# Motorsteuerung_v3.net
KiCad netlist of a schematic drawn in EAGLE
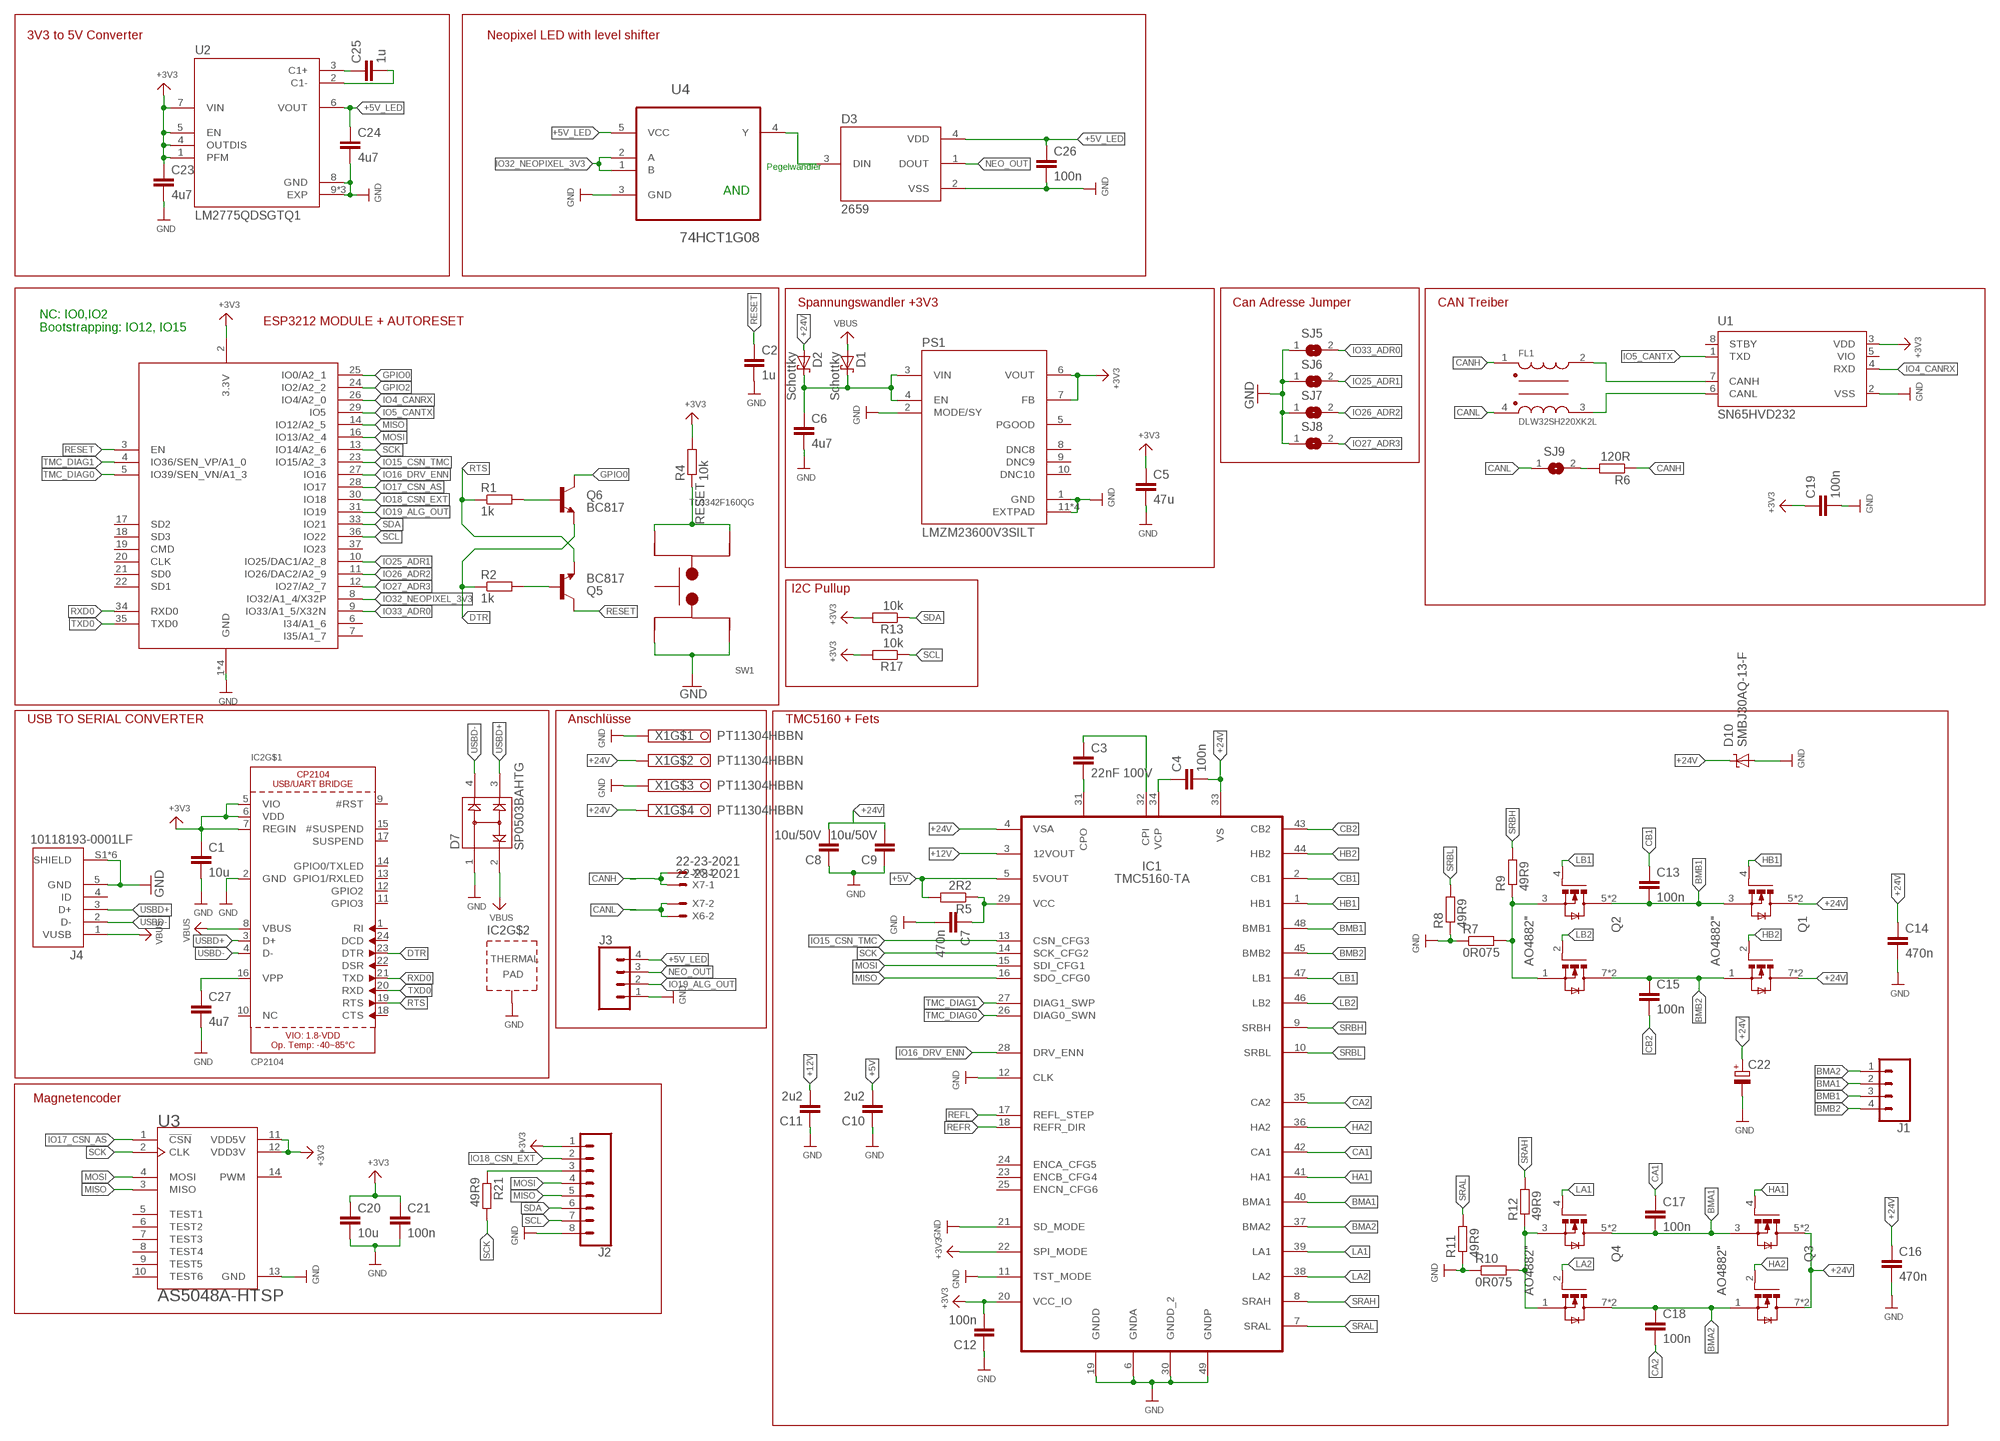
[diagram p0: schematic, sheet 1]

(export (version "E")
  (design (tool "Eeschema 10.0.6"))
  (components
    (comp (ref "C1")
      (value "10u")
      (footprint "eagle-import:C0805")
      (libsource (lib "eagle-import") (part "C-EUC0805"))
    )
    (comp (ref "C2")
      (value "1u")
      (footprint "eagle-import:C0805")
      (libsource (lib "eagle-import") (part "C-EUC0805"))
    )
    (comp (ref "C3")
      (value "22nF 100V")
      (footprint "eagle-import:C0805")
      (libsource (lib "eagle-import") (part "C-EUC0805"))
    )
    (comp (ref "C4")
      (value "100n")
      (footprint "eagle-import:C0805")
      (libsource (lib "eagle-import") (part "C-EUC0805"))
    )
    (comp (ref "C5")
      (value "47u")
      (footprint "eagle-import:C0805")
      (libsource (lib "eagle-import") (part "C-EUC0805"))
    )
    (comp (ref "C6")
      (value "4u7")
      (footprint "eagle-import:C0805")
      (libsource (lib "eagle-import") (part "C-EUC0805"))
    )
    (comp (ref "C7")
      (value "470n")
      (footprint "eagle-import:C0805")
      (libsource (lib "eagle-import") (part "C-EUC0805"))
    )
    (comp (ref "C8")
      (value "10u/50V")
      (footprint "eagle-import:C0805")
      (libsource (lib "eagle-import") (part "C-EUC0805"))
    )
    (comp (ref "C9")
      (value "10u/50V")
      (footprint "eagle-import:C0805")
      (libsource (lib "eagle-import") (part "C-EUC0805"))
    )
    (comp (ref "C10")
      (value "2u2")
      (footprint "eagle-import:C0805")
      (libsource (lib "eagle-import") (part "C-EUC0805"))
    )
    (comp (ref "C11")
      (value "2u2")
      (footprint "eagle-import:C0805")
      (libsource (lib "eagle-import") (part "C-EUC0805"))
    )
    (comp (ref "C12")
      (value "100n")
      (footprint "eagle-import:C0805")
      (libsource (lib "eagle-import") (part "C-EUC0805"))
    )
    (comp (ref "C13")
      (value "100n")
      (footprint "eagle-import:C0805")
      (libsource (lib "eagle-import") (part "C-EUC0805"))
    )
    (comp (ref "C14")
      (value "470n")
      (footprint "eagle-import:C0805")
      (libsource (lib "eagle-import") (part "C-EUC0805"))
    )
    (comp (ref "C15")
      (value "100n")
      (footprint "eagle-import:C0805")
      (libsource (lib "eagle-import") (part "C-EUC0805"))
    )
    (comp (ref "C16")
      (value "470n")
      (footprint "eagle-import:C0805")
      (libsource (lib "eagle-import") (part "C-EUC0805"))
    )
    (comp (ref "C17")
      (value "100n")
      (footprint "eagle-import:C0805")
      (libsource (lib "eagle-import") (part "C-EUC0805"))
    )
    (comp (ref "C18")
      (value "100n")
      (footprint "eagle-import:C0805")
      (libsource (lib "eagle-import") (part "C-EUC0805"))
    )
    (comp (ref "C19")
      (value "100n")
      (footprint "eagle-import:C0805")
      (libsource (lib "eagle-import") (part "C-EUC0805"))
    )
    (comp (ref "C20")
      (value "10u")
      (footprint "eagle-import:C0805")
      (libsource (lib "eagle-import") (part "C-EUC0805"))
    )
    (comp (ref "C21")
      (value "100n")
      (footprint "eagle-import:C0805")
      (libsource (lib "eagle-import") (part "C-EUC0805"))
    )
    (comp (ref "C22")
      (value "CPOL-EUE5-10.5")
      (footprint "eagle-import:E5-10,5")
      (libsource (lib "eagle-import") (part "CPOL-EUE5-10.5"))
    )
    (comp (ref "C23")
      (value "4u7")
      (footprint "eagle-import:C0805")
      (libsource (lib "eagle-import") (part "C-EUC0805"))
    )
    (comp (ref "C24")
      (value "4u7")
      (footprint "eagle-import:C0805")
      (libsource (lib "eagle-import") (part "C-EUC0805"))
    )
    (comp (ref "C25")
      (value "1u")
      (footprint "eagle-import:C0805")
      (libsource (lib "eagle-import") (part "C-EUC0805"))
    )
    (comp (ref "C26")
      (value "100n")
      (footprint "eagle-import:C0805")
      (libsource (lib "eagle-import") (part "C-EUC0805"))
    )
    (comp (ref "C27")
      (value "4u7")
      (footprint "eagle-import:C0805")
      (libsource (lib "eagle-import") (part "C-EUC0805"))
    )
    (comp (ref "D1")
      (value "Schottky")
      (footprint "eagle-import:SMB")
      (libsource (lib "eagle-import") (part "SCHOTTKY-DIODESMD"))
    )
    (comp (ref "D2")
      (value "Schottky")
      (footprint "eagle-import:SMB")
      (libsource (lib "eagle-import") (part "SCHOTTKY-DIODESMD"))
    )
    (comp (ref "D3")
      (value "2659")
      (footprint "eagle-import:2659")
      (fields (field (name "MF") "Adafruit Industries"))
      (libsource (lib "eagle-import") (part "2659"))
    )
    (comp (ref "D7")
      (value "SP0503BAHTG")
      (footprint "eagle-import:SOT143")
      (fields (field (name "MF") "Littelfuse Inc."))
      (libsource (lib "eagle-import") (part "SP0503BAHTG"))
    )
    (comp (ref "D10")
      (value "SMBJ30AQ-13-F")
      (footprint "eagle-import:SMBJ")
      (libsource (lib "eagle-import") (part "SUPPRESSOR-SMBJ"))
    )
    (comp (ref "FL1")
      (value "DLW32SH220XK2L")
      (footprint "eagle-import:FIL_DLW32SH110XK2L")
      (fields (field (name "MF") "Murata") (field (name "MP") "DLW32SH110XK2L"))
      (libsource (lib "eagle-import") (part "DLW32SH110XK2L"))
    )
    (comp (ref "IC1")
      (value "TMC5160-TA")
      (footprint "eagle-import:TQFP48-EP")
      (fields (field (name "MF") "Trinamic Motion"))
      (libsource (lib "eagle-import") (part "TMC5160-TA"))
    )
    (comp (ref "IC2")
      (value "CP2104")
      (footprint "eagle-import:QFN24_4MM_SMSC")
      (libsource (lib "eagle-import") (part "CP2104"))
    )
    (comp (ref "J1")
      (value "CONN_04")
      (footprint "eagle-import:1X04")
      (libsource (lib "eagle-import") (part "CONN_04"))
    )
    (comp (ref "J2")
      (value "CONN_08BM08B-SRSS-TB")
      (footprint "eagle-import:BM08B-SRSS-TB")
      (libsource (lib "eagle-import") (part "CONN_08BM08B-SRSS-TB"))
    )
    (comp (ref "J3")
      (value "CONN_041.27MM")
      (footprint "eagle-import:1X04_1.27MM")
      (libsource (lib "eagle-import") (part "CONN_041.27MM"))
    )
    (comp (ref "J4")
      (value "10118193-0001LF")
      (footprint "eagle-import:FCI_10118193-0001LF")
      (fields (field (name "MF") "Amphenol ICC (FCI)"))
      (libsource (lib "eagle-import") (part "10118193-0001LF"))
    )
    (comp (ref "PS1")
      (value "LMZM23600V3SILT")
      (footprint "eagle-import:CONV_LMZM23600V3SILT")
      (fields (field (name "MF") "Texas Instruments"))
      (libsource (lib "eagle-import") (part "LMZM23600V3SILT"))
    )
    (comp (ref "Q1")
      (value "AO4882\"")
      (footprint "eagle-import:SOIC8")
      (libsource (lib "eagle-import") (part "AO4882{dblquote}"))
    )
    (comp (ref "Q2")
      (value "AO4882\"")
      (footprint "eagle-import:SOIC8")
      (libsource (lib "eagle-import") (part "AO4882{dblquote}"))
    )
    (comp (ref "Q3")
      (value "AO4882\"")
      (footprint "eagle-import:SOIC8")
      (libsource (lib "eagle-import") (part "AO4882{dblquote}"))
    )
    (comp (ref "Q4")
      (value "AO4882\"")
      (footprint "eagle-import:SOIC8")
      (libsource (lib "eagle-import") (part "AO4882{dblquote}"))
    )
    (comp (ref "Q5")
      (value "BC817")
      (footprint "eagle-import:SOT23-3")
      (libsource (lib "eagle-import") (part "TRANSISTOR_NPNSOT23-3"))
    )
    (comp (ref "Q6")
      (value "BC817")
      (footprint "eagle-import:SOT23-3")
      (libsource (lib "eagle-import") (part "TRANSISTOR_NPNSOT23-3"))
    )
    (comp (ref "R1")
      (value "1k")
      (footprint "eagle-import:R0805")
      (libsource (lib "eagle-import") (part "R-EU_R0805"))
    )
    (comp (ref "R2")
      (value "1k")
      (footprint "eagle-import:R0805")
      (libsource (lib "eagle-import") (part "R-EU_R0805"))
    )
    (comp (ref "R4")
      (value "10k")
      (footprint "eagle-import:R0805")
      (libsource (lib "eagle-import") (part "R-EU_R0805"))
    )
    (comp (ref "R5")
      (value "2R2")
      (footprint "eagle-import:R0805")
      (libsource (lib "eagle-import") (part "R-EU_R0805"))
    )
    (comp (ref "R6")
      (value "120R")
      (footprint "eagle-import:R0805")
      (libsource (lib "eagle-import") (part "R-EU_R0805"))
    )
    (comp (ref "R7")
      (value "0R075")
      (footprint "eagle-import:R1206")
      (libsource (lib "eagle-import") (part "R-EU_R1206"))
    )
    (comp (ref "R8")
      (value "49R9")
      (footprint "eagle-import:R0805")
      (libsource (lib "eagle-import") (part "R-EU_R0805"))
    )
    (comp (ref "R9")
      (value "49R9")
      (footprint "eagle-import:R0805")
      (libsource (lib "eagle-import") (part "R-EU_R0805"))
    )
    (comp (ref "R10")
      (value "0R075")
      (footprint "eagle-import:R1206")
      (libsource (lib "eagle-import") (part "R-EU_R1206"))
    )
    (comp (ref "R11")
      (value "49R9")
      (footprint "eagle-import:R0805")
      (libsource (lib "eagle-import") (part "R-EU_R0805"))
    )
    (comp (ref "R12")
      (value "49R9")
      (footprint "eagle-import:R0805")
      (libsource (lib "eagle-import") (part "R-EU_R0805"))
    )
    (comp (ref "R13")
      (value "10k")
      (footprint "eagle-import:R0805")
      (libsource (lib "eagle-import") (part "R-EU_R0805"))
    )
    (comp (ref "R17")
      (value "10k")
      (footprint "eagle-import:R0805")
      (libsource (lib "eagle-import") (part "R-EU_R0805"))
    )
    (comp (ref "R21")
      (value "49R9")
      (footprint "eagle-import:R0805")
      (libsource (lib "eagle-import") (part "R-EU_R0805"))
    )
    (comp (ref "SJ5") (value "SJ") (footprint "eagle-import:SJ") (libsource (lib "eagle-import") (part "SJ")))
    (comp (ref "SJ6") (value "SJ") (footprint "eagle-import:SJ") (libsource (lib "eagle-import") (part "SJ")))
    (comp (ref "SJ7") (value "SJ") (footprint "eagle-import:SJ") (libsource (lib "eagle-import") (part "SJ")))
    (comp (ref "SJ8") (value "SJ") (footprint "eagle-import:SJ") (libsource (lib "eagle-import") (part "SJ")))
    (comp (ref "SJ9") (value "SJ") (footprint "eagle-import:SJ") (libsource (lib "eagle-import") (part "SJ")))
    (comp (ref "SW1")
      (value "TL3342F160QG")
      (footprint "eagle-import:SW_TL3342F160QG")
      (fields (field (name "MF") "E-Switch"))
      (libsource (lib "eagle-import") (part "TL3342F160QG"))
    )
    (comp (ref "U1")
      (value "SN65HVD232")
      (footprint "eagle-import:SOIC127P600X175-8N")
      (fields (field (name "MF") "Microchip") (field (name "MP") "MCP2562-E/SN"))
      (libsource (lib "eagle-import") (part "MCP2562-E/SN"))
    )
    (comp (ref "U2")
      (value "LM2775QDSGTQ1")
      (footprint "eagle-import:SON50P200X200X80-9N")
      (fields (field (name "MF") "Texas Instruments"))
      (libsource (lib "eagle-import") (part "LM2775QDSGTQ1"))
    )
    (comp (ref "U3")
      (value "AS5048A-HTSP")
      (footprint "eagle-import:SOP65P640X120-14N")
      (fields (field (name "MF") "ams"))
      (libsource (lib "eagle-import") (part "AS5048A-HTSP"))
    )
    (comp (ref "U4")
      (value "74HCT1G08")
      (footprint "eagle-import:SOT65P210X110-5N")
      (fields (field (name "MF") "Nexperia") (field (name "MP") "74LVC1G00GW"))
      (libsource (lib "eagle-import") (part "74LVC1G00GW"))
    )
    (comp (ref "X1")
      (value "PT11304HBBN")
      (footprint "eagle-import:TYP184_FT")
      (libsource (lib "eagle-import") (part "TYP184"))
    )
    (comp (ref "X2")
      (value "ESP32_WROOM32_SKINNY")
      (footprint "eagle-import:WROOM32_SKINNY")
      (libsource (lib "eagle-import") (part "ESP32_WROOM32_SKINNY"))
    )
    (comp (ref "X6")
      (value "22-23-2021")
      (footprint "eagle-import:22-23-2021")
      (fields (field (name "MF") "MOLEX"))
      (libsource (lib "eagle-import") (part "22-23-2021"))
    )
    (comp (ref "X7")
      (value "22-23-2021")
      (footprint "eagle-import:22-23-2021")
      (fields (field (name "MF") "MOLEX"))
      (libsource (lib "eagle-import") (part "22-23-2021"))
    )
  )
  (nets
    (net (code "1") (name "+3V3") (class "Default")
      (node (ref "C1") (pin "1") (pinfunction "1_1") (pintype "passive"))
      (node (ref "C12") (pin "2") (pinfunction "2_2") (pintype "passive"))
      (node (ref "C19") (pin "1") (pinfunction "1_1") (pintype "passive"))
      (node (ref "C20") (pin "1") (pinfunction "1_1") (pintype "passive"))
      (node (ref "C21") (pin "1") (pinfunction "1_1") (pintype "passive"))
      (node (ref "C23") (pin "1") (pinfunction "1_1") (pintype "passive"))
      (node (ref "C5") (pin "1") (pinfunction "1_1") (pintype "passive"))
      (node (ref "IC1") (pin "20") (pinfunction "VCC_IO_20") (pintype "power_in"))
      (node (ref "IC1") (pin "22") (pinfunction "SPI_MODE_22") (pintype "input"))
      (node (ref "IC2") (pin "5") (pinfunction "VIO_5") (pintype "power_in"))
      (node (ref "IC2") (pin "6") (pinfunction "VDD_6") (pintype "power_in"))
      (node (ref "IC2") (pin "7") (pinfunction "REGIN_7") (pintype "power_in"))
      (node (ref "J2") (pin "1") (pinfunction "1_1") (pintype "passive"))
      (node (ref "PS1") (pin "6") (pinfunction "VOUT_6") (pintype "output"))
      (node (ref "PS1") (pin "7") (pinfunction "FB_7") (pintype "input"))
      (node (ref "R13") (pin "2") (pinfunction "2_2") (pintype "passive"))
      (node (ref "R17") (pin "2") (pinfunction "2_2") (pintype "passive"))
      (node (ref "R4") (pin "2") (pinfunction "2_2") (pintype "passive"))
      (node (ref "U1") (pin "3") (pinfunction "VDD_3") (pintype "power_in"))
      (node (ref "U2") (pin "1") (pinfunction "PFM_1") (pintype "input"))
      (node (ref "U2") (pin "4") (pinfunction "OUTDIS_4") (pintype "input"))
      (node (ref "U2") (pin "5") (pinfunction "EN_5") (pintype "input"))
      (node (ref "U2") (pin "7") (pinfunction "VIN_7") (pintype "input"))
      (node (ref "U3") (pin "11") (pinfunction "VDD5V_11") (pintype "power_in"))
      (node (ref "U3") (pin "12") (pinfunction "VDD3V_12") (pintype "power_in"))
      (node (ref "X2") (pin "2") (pinfunction "3.3V_2") (pintype "passive"))
    )
    (net (code "2") (name "+5V") (class "Default")
      (node (ref "C10") (pin "2") (pinfunction "2_2") (pintype "passive"))
      (node (ref "IC1") (pin "5") (pinfunction "5VOUT_5") (pintype "bidirectional"))
      (node (ref "R5") (pin "2") (pinfunction "2_2") (pintype "passive"))
    )
    (net (code "3") (name "+5V_LED") (class "Default")
      (node (ref "C24") (pin "1") (pinfunction "1_1") (pintype "passive"))
      (node (ref "C26") (pin "1") (pinfunction "1_1") (pintype "passive"))
      (node (ref "D3") (pin "4") (pinfunction "VDD_4") (pintype "power_in"))
      (node (ref "J3") (pin "4") (pinfunction "4_4") (pintype "passive"))
      (node (ref "U2") (pin "6") (pinfunction "VOUT_6") (pintype "output"))
      (node (ref "U4") (pin "5") (pinfunction "VCC_5") (pintype "power_in"))
    )
    (net (code "4") (name "+12V") (class "Default")
      (node (ref "C11") (pin "2") (pinfunction "2_2") (pintype "passive"))
      (node (ref "IC1") (pin "3") (pinfunction "12VOUT_3") (pintype "bidirectional"))
    )
    (net (code "5") (name "+24V") (class "Default")
      (node (ref "C14") (pin "1") (pinfunction "1_1") (pintype "passive"))
      (node (ref "C16") (pin "1") (pinfunction "1_1") (pintype "passive"))
      (node (ref "C22") (pin "+") (pinfunction "+_+") (pintype "passive"))
      (node (ref "C4") (pin "2") (pinfunction "2_2") (pintype "passive"))
      (node (ref "C8") (pin "2") (pinfunction "2_2") (pintype "passive"))
      (node (ref "C9") (pin "2") (pinfunction "2_2") (pintype "passive"))
      (node (ref "D10") (pin "C") (pinfunction "C_C") (pintype "passive"))
      (node (ref "D2") (pin "A") (pinfunction "A_A") (pintype "passive"))
      (node (ref "IC1") (pin "33") (pinfunction "VS_33") (pintype "power_in"))
      (node (ref "IC1") (pin "4") (pinfunction "VSA_4") (pintype "power_in"))
      (node (ref "Q1") (pin "5") (pinfunction "D1_5") (pintype "passive"))
      (node (ref "Q1") (pin "6") (pinfunction "D1_6") (pintype "passive"))
      (node (ref "Q1") (pin "7") (pinfunction "D2_7") (pintype "passive"))
      (node (ref "Q1") (pin "8") (pinfunction "D2_8") (pintype "passive"))
      (node (ref "Q3") (pin "5") (pinfunction "D1_5") (pintype "passive"))
      (node (ref "Q3") (pin "6") (pinfunction "D1_6") (pintype "passive"))
      (node (ref "Q3") (pin "7") (pinfunction "D2_7") (pintype "passive"))
      (node (ref "Q3") (pin "8") (pinfunction "D2_8") (pintype "passive"))
      (node (ref "X1") (pin "2") (pinfunction "K_2") (pintype "passive"))
      (node (ref "X1") (pin "4") (pinfunction "K_4") (pintype "passive"))
    )
    (net (code "6") (name "/VIO") (class "Default")
      (node (ref "U1") (pin "5") (pinfunction "VIO_5") (pintype "power_in"))
    )
    (net (code "7") (name "BMA1") (class "Default")
      (node (ref "C17") (pin "2") (pinfunction "2_2") (pintype "passive"))
      (node (ref "IC1") (pin "40") (pinfunction "BMA1_40") (pintype "input"))
      (node (ref "J1") (pin "2") (pinfunction "2_2") (pintype "passive"))
      (node (ref "Q3") (pin "3") (pinfunction "S1_3") (pintype "passive"))
      (node (ref "Q4") (pin "5") (pinfunction "D1_5") (pintype "passive"))
      (node (ref "Q4") (pin "6") (pinfunction "D1_6") (pintype "passive"))
    )
    (net (code "8") (name "BMA2") (class "Default")
      (node (ref "C18") (pin "1") (pinfunction "1_1") (pintype "passive"))
      (node (ref "IC1") (pin "37") (pinfunction "BMA2_37") (pintype "input"))
      (node (ref "J1") (pin "1") (pinfunction "1_1") (pintype "passive"))
      (node (ref "Q3") (pin "1") (pinfunction "S2_1") (pintype "passive"))
      (node (ref "Q4") (pin "7") (pinfunction "D2_7") (pintype "passive"))
      (node (ref "Q4") (pin "8") (pinfunction "D2_8") (pintype "passive"))
    )
    (net (code "9") (name "BMB1") (class "Default")
      (node (ref "C13") (pin "2") (pinfunction "2_2") (pintype "passive"))
      (node (ref "IC1") (pin "48") (pinfunction "BMB1_48") (pintype "input"))
      (node (ref "J1") (pin "3") (pinfunction "3_3") (pintype "passive"))
      (node (ref "Q1") (pin "3") (pinfunction "S1_3") (pintype "passive"))
      (node (ref "Q2") (pin "5") (pinfunction "D1_5") (pintype "passive"))
      (node (ref "Q2") (pin "6") (pinfunction "D1_6") (pintype "passive"))
    )
    (net (code "10") (name "BMB2") (class "Default")
      (node (ref "C15") (pin "1") (pinfunction "1_1") (pintype "passive"))
      (node (ref "IC1") (pin "45") (pinfunction "BMB2_45") (pintype "input"))
      (node (ref "J1") (pin "4") (pinfunction "4_4") (pintype "passive"))
      (node (ref "Q1") (pin "1") (pinfunction "S2_1") (pintype "passive"))
      (node (ref "Q2") (pin "7") (pinfunction "D2_7") (pintype "passive"))
      (node (ref "Q2") (pin "8") (pinfunction "D2_8") (pintype "passive"))
    )
    (net (code "11") (name "CA1") (class "Default")
      (node (ref "C17") (pin "1") (pinfunction "1_1") (pintype "passive"))
      (node (ref "IC1") (pin "42") (pinfunction "CA1_42") (pintype "input"))
    )
    (net (code "12") (name "CA2") (class "Default")
      (node (ref "C18") (pin "2") (pinfunction "2_2") (pintype "passive"))
      (node (ref "IC1") (pin "35") (pinfunction "CA2_35") (pintype "input"))
    )
    (net (code "13") (name "CANH") (class "Default")
      (node (ref "FL1") (pin "1") (pinfunction "1_1") (pintype "passive"))
      (node (ref "R6") (pin "1") (pinfunction "1_1") (pintype "passive"))
      (node (ref "X6") (pin "1") (pinfunction "S_1") (pintype "passive"))
      (node (ref "X7") (pin "1") (pinfunction "S_1") (pintype "passive"))
    )
    (net (code "14") (name "CANL") (class "Default")
      (node (ref "FL1") (pin "4") (pinfunction "4_4") (pintype "passive"))
      (node (ref "SJ9") (pin "1") (pinfunction "1_1") (pintype "passive"))
      (node (ref "X6") (pin "2") (pinfunction "S_2") (pintype "passive"))
      (node (ref "X7") (pin "2") (pinfunction "S_2") (pintype "passive"))
    )
    (net (code "15") (name "CB1") (class "Default")
      (node (ref "C13") (pin "1") (pinfunction "1_1") (pintype "passive"))
      (node (ref "IC1") (pin "2") (pinfunction "CB1_2") (pintype "input"))
    )
    (net (code "16") (name "CB2") (class "Default")
      (node (ref "C15") (pin "2") (pinfunction "2_2") (pintype "passive"))
      (node (ref "IC1") (pin "43") (pinfunction "CB2_43") (pintype "input"))
    )
    (net (code "17") (name "DTR") (class "Default")
      (node (ref "IC2") (pin "23") (pinfunction "DTR_23") (pintype "output"))
      (node (ref "Q6") (pin "2") (pinfunction "E_2") (pintype "passive"))
      (node (ref "R2") (pin "1") (pinfunction "1_1") (pintype "passive"))
    )
    (net (code "18") (name "GND") (class "Default")
      (node (ref "C1") (pin "2") (pinfunction "2_2") (pintype "passive"))
      (node (ref "C10") (pin "1") (pinfunction "1_1") (pintype "passive"))
      (node (ref "C11") (pin "1") (pinfunction "1_1") (pintype "passive"))
      (node (ref "C12") (pin "1") (pinfunction "1_1") (pintype "passive"))
      (node (ref "C14") (pin "2") (pinfunction "2_2") (pintype "passive"))
      (node (ref "C16") (pin "2") (pinfunction "2_2") (pintype "passive"))
      (node (ref "C19") (pin "2") (pinfunction "2_2") (pintype "passive"))
      (node (ref "C2") (pin "2") (pinfunction "2_2") (pintype "passive"))
      (node (ref "C20") (pin "2") (pinfunction "2_2") (pintype "passive"))
      (node (ref "C21") (pin "2") (pinfunction "2_2") (pintype "passive"))
      (node (ref "C22") (pin "-") (pinfunction "-_-") (pintype "passive"))
      (node (ref "C23") (pin "2") (pinfunction "2_2") (pintype "passive"))
      (node (ref "C24") (pin "2") (pinfunction "2_2") (pintype "passive"))
      (node (ref "C26") (pin "2") (pinfunction "2_2") (pintype "passive"))
      (node (ref "C27") (pin "2") (pinfunction "2_2") (pintype "passive"))
      (node (ref "C5") (pin "2") (pinfunction "2_2") (pintype "passive"))
      (node (ref "C6") (pin "2") (pinfunction "2_2") (pintype "passive"))
      (node (ref "C7") (pin "2") (pinfunction "2_2") (pintype "passive"))
      (node (ref "C8") (pin "1") (pinfunction "1_1") (pintype "passive"))
      (node (ref "C9") (pin "1") (pinfunction "1_1") (pintype "passive"))
      (node (ref "D10") (pin "A") (pinfunction "A_A") (pintype "passive"))
      (node (ref "D3") (pin "2") (pinfunction "VSS_2") (pintype "power_in"))
      (node (ref "D7") (pin "1") (pinfunction "1_1") (pintype "passive"))
      (node (ref "IC1") (pin "11") (pinfunction "TST_MODE_11") (pintype "input"))
      (node (ref "IC1") (pin "12") (pinfunction "CLK_12") (pintype "input"))
      (node (ref "IC1") (pin "19") (pinfunction "GNDD_19") (pintype "power_in"))
      (node (ref "IC1") (pin "21") (pinfunction "SD_MODE_21") (pintype "input"))
      (node (ref "IC1") (pin "30") (pinfunction "GNDD_2_30") (pintype "power_in"))
      (node (ref "IC1") (pin "49") (pinfunction "GNDP_49") (pintype "power_in"))
      (node (ref "IC1") (pin "6") (pinfunction "GNDA_6") (pintype "power_in"))
      (node (ref "IC2") (pin "2") (pinfunction "GND_2") (pintype "power_in"))
      (node (ref "IC2") (pin "THERM") (pinfunction "TP_THERM") (pintype "power_in"))
      (node (ref "J2") (pin "8") (pinfunction "8_8") (pintype "passive"))
      (node (ref "J3") (pin "1") (pinfunction "1_1") (pintype "passive"))
      (node (ref "J4") (pin "5") (pinfunction "GND_5") (pintype "passive"))
      (node (ref "J4") (pin "S1") (pinfunction "SHIELD_S1") (pintype "passive"))
      (node (ref "J4") (pin "S2") (pinfunction "SHIELD_S2") (pintype "passive"))
      (node (ref "J4") (pin "S3") (pinfunction "SHIELD_S3") (pintype "passive"))
      (node (ref "J4") (pin "S4") (pinfunction "SHIELD_S4") (pintype "passive"))
      (node (ref "J4") (pin "S5") (pinfunction "SHIELD_S5") (pintype "passive"))
      (node (ref "J4") (pin "S6") (pinfunction "SHIELD_S6") (pintype "passive"))
      (node (ref "PS1") (pin "1") (pinfunction "GND_1") (pintype "power_in"))
      (node (ref "PS1") (pin "11") (pinfunction "EXTPAD_11") (pintype "power_in"))
      (node (ref "PS1") (pin "11_1") (pinfunction "EXTPAD_11_1") (pintype "power_in"))
      (node (ref "PS1") (pin "11_2") (pinfunction "EXTPAD_11_2") (pintype "power_in"))
      (node (ref "PS1") (pin "11_3") (pinfunction "EXTPAD_11_3") (pintype "power_in"))
      (node (ref "PS1") (pin "2") (pinfunction "MODE/SY_2") (pintype "input"))
      (node (ref "R10") (pin "1") (pinfunction "1_1") (pintype "passive"))
      (node (ref "R11") (pin "1") (pinfunction "1_1") (pintype "passive"))
      (node (ref "R7") (pin "1") (pinfunction "1_1") (pintype "passive"))
      (node (ref "R8") (pin "1") (pinfunction "1_1") (pintype "passive"))
      (node (ref "SJ5") (pin "1") (pinfunction "1_1") (pintype "passive"))
      (node (ref "SJ6") (pin "1") (pinfunction "1_1") (pintype "passive"))
      (node (ref "SJ7") (pin "1") (pinfunction "1_1") (pintype "passive"))
      (node (ref "SJ8") (pin "1") (pinfunction "1_1") (pintype "passive"))
      (node (ref "SW1") (pin "3") (pinfunction "3_3") (pintype "passive"))
      (node (ref "SW1") (pin "4") (pinfunction "4_4") (pintype "passive"))
      (node (ref "U1") (pin "2") (pinfunction "VSS_2") (pintype "power_in"))
      (node (ref "U2") (pin "8") (pinfunction "GND_8") (pintype "power_in"))
      (node (ref "U2") (pin "9") (pinfunction "EXP_9") (pintype "power_in"))
      (node (ref "U2") (pin "9_1") (pinfunction "EXP_9_1") (pintype "power_in"))
      (node (ref "U2") (pin "9_2") (pinfunction "EXP_9_2") (pintype "power_in"))
      (node (ref "U3") (pin "13") (pinfunction "GND_13") (pintype "passive"))
      (node (ref "U4") (pin "3") (pinfunction "GND_3") (pintype "passive"))
      (node (ref "X1") (pin "1") (pinfunction "K_1") (pintype "passive"))
      (node (ref "X1") (pin "3") (pinfunction "K_3") (pintype "passive"))
      (node (ref "X2") (pin "1") (pinfunction "GND_1") (pintype "passive"))
      (node (ref "X2") (pin "15") (pinfunction "GND_15") (pintype "passive"))
      (node (ref "X2") (pin "38") (pinfunction "GND_38") (pintype "passive"))
      (node (ref "X2") (pin "P$1") (pinfunction "GND_P$1") (pintype "passive"))
    )
    (net (code "19") (name "GPIO0") (class "Default")
      (node (ref "Q6") (pin "3") (pinfunction "C_3") (pintype "passive"))
      (node (ref "X2") (pin "25") (pinfunction "IO0/A2_1_25") (pintype "bidirectional"))
    )
    (net (code "20") (name "GPIO2") (class "Default")
      (node (ref "X2") (pin "24") (pinfunction "IO2/A2_2_24") (pintype "bidirectional"))
    )
    (net (code "21") (name "HA1") (class "Default")
      (node (ref "IC1") (pin "41") (pinfunction "HA1_41") (pintype "output"))
      (node (ref "Q3") (pin "4") (pinfunction "G1_4") (pintype "passive"))
    )
    (net (code "22") (name "HA2") (class "Default")
      (node (ref "IC1") (pin "36") (pinfunction "HA2_36") (pintype "output"))
      (node (ref "Q3") (pin "2") (pinfunction "G2_2") (pintype "passive"))
    )
    (net (code "23") (name "HB1") (class "Default")
      (node (ref "IC1") (pin "1") (pinfunction "HB1_1") (pintype "output"))
      (node (ref "Q1") (pin "4") (pinfunction "G1_4") (pintype "passive"))
    )
    (net (code "24") (name "HB2") (class "Default")
      (node (ref "IC1") (pin "44") (pinfunction "HB2_44") (pintype "output"))
      (node (ref "Q1") (pin "2") (pinfunction "G2_2") (pintype "passive"))
    )
    (net (code "25") (name "IO4_CANRX") (class "Default")
      (node (ref "U1") (pin "4") (pinfunction "RXD_4") (pintype "output"))
      (node (ref "X2") (pin "26") (pinfunction "IO4/A2_0_26") (pintype "bidirectional"))
    )
    (net (code "26") (name "IO5_CANTX") (class "Default")
      (node (ref "U1") (pin "1") (pinfunction "TXD_1") (pintype "input"))
      (node (ref "X2") (pin "29") (pinfunction "IO5_29") (pintype "bidirectional"))
    )
    (net (code "27") (name "IO15_CSN_TMC") (class "Default")
      (node (ref "IC1") (pin "13") (pinfunction "CSN_CFG3_13") (pintype "input"))
      (node (ref "X2") (pin "23") (pinfunction "IO15/A2_3_23") (pintype "bidirectional"))
    )
    (net (code "28") (name "IO16_DRV_ENN") (class "Default")
      (node (ref "IC1") (pin "28") (pinfunction "DRV_ENN_28") (pintype "input"))
      (node (ref "X2") (pin "27") (pinfunction "IO16_27") (pintype "bidirectional"))
    )
    (net (code "29") (name "IO17_CSN_AS") (class "Default")
      (node (ref "U3") (pin "1") (pinfunction "~{CSN}_1") (pintype "input"))
      (node (ref "X2") (pin "28") (pinfunction "IO17_28") (pintype "bidirectional"))
    )
    (net (code "30") (name "IO18_CSN_EXT") (class "Default")
      (node (ref "J2") (pin "2") (pinfunction "2_2") (pintype "passive"))
      (node (ref "X2") (pin "30") (pinfunction "IO18_30") (pintype "bidirectional"))
    )
    (net (code "31") (name "IO19_ALG_OUT") (class "Default")
      (node (ref "J3") (pin "2") (pinfunction "2_2") (pintype "passive"))
      (node (ref "X2") (pin "31") (pinfunction "IO19_31") (pintype "bidirectional"))
    )
    (net (code "32") (name "IO25_ADR1") (class "Default")
      (node (ref "SJ6") (pin "2") (pinfunction "2_2") (pintype "passive"))
      (node (ref "X2") (pin "10") (pinfunction "IO25/DAC1/A2_8_10") (pintype "bidirectional"))
    )
    (net (code "33") (name "IO26_ADR2") (class "Default")
      (node (ref "SJ7") (pin "2") (pinfunction "2_2") (pintype "passive"))
      (node (ref "X2") (pin "11") (pinfunction "IO26/DAC2/A2_9_11") (pintype "bidirectional"))
    )
    (net (code "34") (name "IO27_ADR3") (class "Default")
      (node (ref "SJ8") (pin "2") (pinfunction "2_2") (pintype "passive"))
      (node (ref "X2") (pin "12") (pinfunction "IO27/A2_7_12") (pintype "bidirectional"))
    )
    (net (code "35") (name "IO32_NEOPIXEL_3V3") (class "Default")
      (node (ref "U4") (pin "1") (pinfunction "B_1") (pintype "input"))
      (node (ref "U4") (pin "2") (pinfunction "A_2") (pintype "input"))
      (node (ref "X2") (pin "8") (pinfunction "IO32/A1_4/X32P_8") (pintype "bidirectional"))
    )
    (net (code "36") (name "IO33_ADR0") (class "Default")
      (node (ref "SJ5") (pin "2") (pinfunction "2_2") (pintype "passive"))
      (node (ref "X2") (pin "9") (pinfunction "IO33/A1_5/X32N_9") (pintype "bidirectional"))
    )
    (net (code "37") (name "LA1") (class "Default")
      (node (ref "IC1") (pin "39") (pinfunction "LA1_39") (pintype "output"))
      (node (ref "Q4") (pin "4") (pinfunction "G1_4") (pintype "passive"))
    )
    (net (code "38") (name "LA2") (class "Default")
      (node (ref "IC1") (pin "38") (pinfunction "LA2_38") (pintype "output"))
      (node (ref "Q4") (pin "2") (pinfunction "G2_2") (pintype "passive"))
    )
    (net (code "39") (name "LB1") (class "Default")
      (node (ref "IC1") (pin "47") (pinfunction "LB1_47") (pintype "output"))
      (node (ref "Q2") (pin "4") (pinfunction "G1_4") (pintype "passive"))
    )
    (net (code "40") (name "LB2") (class "Default")
      (node (ref "IC1") (pin "46") (pinfunction "LB2_46") (pintype "output"))
      (node (ref "Q2") (pin "2") (pinfunction "G2_2") (pintype "passive"))
    )
    (net (code "41") (name "MISO") (class "Default")
      (node (ref "IC1") (pin "16") (pinfunction "SDO_CFG0_16") (pintype "output"))
      (node (ref "J2") (pin "5") (pinfunction "5_5") (pintype "passive"))
      (node (ref "U3") (pin "3") (pinfunction "MISO_3") (pintype "bidirectional"))
      (node (ref "X2") (pin "14") (pinfunction "IO12/A2_5_14") (pintype "bidirectional"))
    )
    (net (code "42") (name "MOSI") (class "Default")
      (node (ref "IC1") (pin "15") (pinfunction "SDI_CFG1_15") (pintype "input"))
      (node (ref "J2") (pin "4") (pinfunction "4_4") (pintype "passive"))
      (node (ref "U3") (pin "4") (pinfunction "MOSI_4") (pintype "input"))
      (node (ref "X2") (pin "16") (pinfunction "IO13/A2_4_16") (pintype "bidirectional"))
    )
    (net (code "43") (name "NEO_OUT") (class "Default")
      (node (ref "D3") (pin "1") (pinfunction "DOUT_1") (pintype "output"))
      (node (ref "J3") (pin "3") (pinfunction "3_3") (pintype "passive"))
    )
    (net (code "44") (name "Net-(D3-DIN)") (class "Default")
      (node (ref "D3") (pin "3") (pinfunction "DIN_3") (pintype "input"))
      (node (ref "U4") (pin "4") (pinfunction "Y_4") (pintype "output"))
    )
    (net (code "45") (name "Net-(IC1-CPI)") (class "Default")
      (node (ref "C3") (pin "1") (pinfunction "1_1") (pintype "passive"))
      (node (ref "IC1") (pin "32") (pinfunction "CPI_32") (pintype "input"))
    )
    (net (code "46") (name "Net-(IC1-CPO)") (class "Default")
      (node (ref "C3") (pin "2") (pinfunction "2_2") (pintype "passive"))
      (node (ref "IC1") (pin "31") (pinfunction "CPO_31") (pintype "input"))
    )
    (net (code "47") (name "Net-(IC1-VCC)") (class "Default")
      (node (ref "C7") (pin "1") (pinfunction "1_1") (pintype "passive"))
      (node (ref "IC1") (pin "29") (pinfunction "VCC_29") (pintype "power_in"))
      (node (ref "R5") (pin "1") (pinfunction "1_1") (pintype "passive"))
    )
    (net (code "48") (name "Net-(IC1-VCP)") (class "Default")
      (node (ref "C4") (pin "1") (pinfunction "1_1") (pintype "passive"))
      (node (ref "IC1") (pin "34") (pinfunction "VCP_34") (pintype "input"))
    )
    (net (code "49") (name "Net-(IC2A-VPP)") (class "Default")
      (node (ref "C27") (pin "1") (pinfunction "1_1") (pintype "passive"))
      (node (ref "IC2") (pin "16") (pinfunction "VPP_16") (pintype "bidirectional"))
    )
    (net (code "50") (name "Net-(J2-Pad3)") (class "Default")
      (node (ref "J2") (pin "3") (pinfunction "3_3") (pintype "passive"))
      (node (ref "R21") (pin "1") (pinfunction "1_1") (pintype "passive"))
    )
    (net (code "51") (name "Net-(PS1-EN)") (class "Default")
      (node (ref "C6") (pin "1") (pinfunction "1_1") (pintype "passive"))
      (node (ref "D1") (pin "C") (pinfunction "C_C") (pintype "passive"))
      (node (ref "D2") (pin "C") (pinfunction "C_C") (pintype "passive"))
      (node (ref "PS1") (pin "3") (pinfunction "VIN_3") (pintype "input"))
      (node (ref "PS1") (pin "4") (pinfunction "EN_4") (pintype "input"))
    )
    (net (code "52") (name "Net-(Q2-S1)") (class "Default")
      (node (ref "Q2") (pin "1") (pinfunction "S2_1") (pintype "passive"))
      (node (ref "Q2") (pin "3") (pinfunction "S1_3") (pintype "passive"))
      (node (ref "R7") (pin "2") (pinfunction "2_2") (pintype "passive"))
      (node (ref "R9") (pin "1") (pinfunction "1_1") (pintype "passive"))
    )
    (net (code "53") (name "Net-(Q4-S1)") (class "Default")
      (node (ref "Q4") (pin "1") (pinfunction "S2_1") (pintype "passive"))
      (node (ref "Q4") (pin "3") (pinfunction "S1_3") (pintype "passive"))
      (node (ref "R10") (pin "2") (pinfunction "2_2") (pintype "passive"))
      (node (ref "R12") (pin "1") (pinfunction "1_1") (pintype "passive"))
    )
    (net (code "54") (name "Net-(Q5-B)") (class "Default")
      (node (ref "Q5") (pin "1") (pinfunction "B_1") (pintype "passive"))
      (node (ref "R2") (pin "2") (pinfunction "2_2") (pintype "passive"))
    )
    (net (code "55") (name "Net-(Q6-B)") (class "Default")
      (node (ref "Q6") (pin "1") (pinfunction "B_1") (pintype "passive"))
      (node (ref "R1") (pin "2") (pinfunction "2_2") (pintype "passive"))
    )
    (net (code "56") (name "Net-(R6-Pad2)") (class "Default")
      (node (ref "R6") (pin "2") (pinfunction "2_2") (pintype "passive"))
      (node (ref "SJ9") (pin "2") (pinfunction "2_2") (pintype "passive"))
    )
    (net (code "57") (name "Net-(U1-CANH)") (class "Default")
      (node (ref "FL1") (pin "2") (pinfunction "2_2") (pintype "passive"))
      (node (ref "U1") (pin "7") (pinfunction "CANH_7") (pintype "input"))
    )
    (net (code "58") (name "Net-(U1-CANL)") (class "Default")
      (node (ref "FL1") (pin "3") (pinfunction "3_3") (pintype "passive"))
      (node (ref "U1") (pin "6") (pinfunction "CANL_6") (pintype "input"))
    )
    (net (code "59") (name "Net-(U2-C1+)") (class "Default")
      (node (ref "C25") (pin "1") (pinfunction "1_1") (pintype "passive"))
      (node (ref "U2") (pin "3") (pinfunction "C1+_3") (pintype "power_in"))
    )
    (net (code "60") (name "Net-(U2-C1-)") (class "Default")
      (node (ref "C25") (pin "2") (pinfunction "2_2") (pintype "passive"))
      (node (ref "U2") (pin "2") (pinfunction "C1-_2") (pintype "power_in"))
    )
    (net (code "61") (name "REFL") (class "Default")
      (node (ref "IC1") (pin "17") (pinfunction "REFL_STEP_17") (pintype "input"))
    )
    (net (code "62") (name "REFR") (class "Default")
      (node (ref "IC1") (pin "18") (pinfunction "REFR_DIR_18") (pintype "input"))
    )
    (net (code "63") (name "RESET") (class "Default")
      (node (ref "C2") (pin "1") (pinfunction "1_1") (pintype "passive"))
      (node (ref "Q5") (pin "3") (pinfunction "C_3") (pintype "passive"))
      (node (ref "R4") (pin "1") (pinfunction "1_1") (pintype "passive"))
      (node (ref "SW1") (pin "1") (pinfunction "1_1") (pintype "passive"))
      (node (ref "SW1") (pin "2") (pinfunction "2_2") (pintype "passive"))
      (node (ref "X2") (pin "3") (pinfunction "EN_3") (pintype "input"))
    )
    (net (code "64") (name "RTS") (class "Default")
      (node (ref "IC2") (pin "19") (pinfunction "RTS_19") (pintype "output"))
      (node (ref "Q5") (pin "2") (pinfunction "E_2") (pintype "passive"))
      (node (ref "R1") (pin "1") (pinfunction "1_1") (pintype "passive"))
    )
    (net (code "65") (name "RXD0") (class "Default")
      (node (ref "IC2") (pin "21") (pinfunction "TXD_21") (pintype "output"))
      (node (ref "X2") (pin "34") (pinfunction "RXD0_34") (pintype "input"))
    )
    (net (code "66") (name "SCK") (class "Default")
      (node (ref "IC1") (pin "14") (pinfunction "SCK_CFG2_14") (pintype "input"))
      (node (ref "R21") (pin "2") (pinfunction "2_2") (pintype "passive"))
      (node (ref "U3") (pin "2") (pinfunction "CLK_2") (pintype "input"))
      (node (ref "X2") (pin "13") (pinfunction "IO14/A2_6_13") (pintype "bidirectional"))
    )
    (net (code "67") (name "SCL") (class "Default")
      (node (ref "J2") (pin "7") (pinfunction "7_7") (pintype "passive"))
      (node (ref "R17") (pin "1") (pinfunction "1_1") (pintype "passive"))
      (node (ref "X2") (pin "36") (pinfunction "IO22_36") (pintype "bidirectional"))
    )
    (net (code "68") (name "SDA") (class "Default")
      (node (ref "J2") (pin "6") (pinfunction "6_6") (pintype "passive"))
      (node (ref "R13") (pin "1") (pinfunction "1_1") (pintype "passive"))
      (node (ref "X2") (pin "33") (pinfunction "IO21_33") (pintype "bidirectional"))
    )
    (net (code "69") (name "SRAH") (class "Default")
      (node (ref "IC1") (pin "8") (pinfunction "SRAH_8") (pintype "input"))
      (node (ref "R12") (pin "2") (pinfunction "2_2") (pintype "passive"))
    )
    (net (code "70") (name "SRAL") (class "Default")
      (node (ref "IC1") (pin "7") (pinfunction "SRAL_7") (pintype "input"))
      (node (ref "R11") (pin "2") (pinfunction "2_2") (pintype "passive"))
    )
    (net (code "71") (name "SRBH") (class "Default")
      (node (ref "IC1") (pin "9") (pinfunction "SRBH_9") (pintype "input"))
      (node (ref "R9") (pin "2") (pinfunction "2_2") (pintype "passive"))
    )
    (net (code "72") (name "SRBL") (class "Default")
      (node (ref "IC1") (pin "10") (pinfunction "SRBL_10") (pintype "input"))
      (node (ref "R8") (pin "2") (pinfunction "2_2") (pintype "passive"))
    )
    (net (code "73") (name "TMC_DIAG0") (class "Default")
      (node (ref "IC1") (pin "26") (pinfunction "DIAG0_SWN_26") (pintype "bidirectional"))
      (node (ref "X2") (pin "5") (pinfunction "IO39/SEN_VN/A1_3_5") (pintype "passive"))
    )
    (net (code "74") (name "TMC_DIAG1") (class "Default")
      (node (ref "IC1") (pin "27") (pinfunction "DIAG1_SWP_27") (pintype "bidirectional"))
      (node (ref "X2") (pin "4") (pinfunction "IO36/SEN_VP/A1_0_4") (pintype "passive"))
    )
    (net (code "75") (name "TXD0") (class "Default")
      (node (ref "IC2") (pin "20") (pinfunction "RXD_20") (pintype "input"))
      (node (ref "X2") (pin "35") (pinfunction "TXD0_35") (pintype "output"))
    )
    (net (code "76") (name "USBD+") (class "Default")
      (node (ref "D7") (pin "3") (pinfunction "3_3") (pintype "passive"))
      (node (ref "IC2") (pin "3") (pinfunction "D+_3") (pintype "bidirectional"))
      (node (ref "J4") (pin "3") (pinfunction "D+_3") (pintype "passive"))
    )
    (net (code "77") (name "USBD-") (class "Default")
      (node (ref "D7") (pin "4") (pinfunction "4_4") (pintype "passive"))
      (node (ref "IC2") (pin "4") (pinfunction "D-_4") (pintype "bidirectional"))
      (node (ref "J4") (pin "2") (pinfunction "D-_2") (pintype "passive"))
    )
    (net (code "78") (name "VBUS") (class "Default")
      (node (ref "D1") (pin "A") (pinfunction "A_A") (pintype "passive"))
      (node (ref "D7") (pin "2") (pinfunction "2_2") (pintype "passive"))
      (node (ref "IC2") (pin "8") (pinfunction "VBUS_8") (pintype "power_in"))
      (node (ref "J4") (pin "1") (pinfunction "VUSB_1") (pintype "passive"))
    )
    (net (code "79") (name "unconnected-(IC1-ENCA_CFG5-Pad24)") (class "Default")
      (node (ref "IC1") (pin "24") (pinfunction "ENCA_CFG5_24") (pintype "input"))
    )
    (net (code "80") (name "unconnected-(IC1-ENCB_CFG4-Pad23)") (class "Default")
      (node (ref "IC1") (pin "23") (pinfunction "ENCB_CFG4_23") (pintype "input"))
    )
    (net (code "81") (name "unconnected-(IC1-ENCN_CFG6-Pad25)") (class "Default")
      (node (ref "IC1") (pin "25") (pinfunction "ENCN_CFG6_25") (pintype "input"))
    )
    (net (code "82") (name "unconnected-(IC2A-#RST-Pad9)") (class "Default")
      (node (ref "IC2") (pin "9") (pinfunction "#RST_9") (pintype "bidirectional"))
    )
    (net (code "83") (name "unconnected-(IC2A-#SUSPEND-Pad15)") (class "Default")
      (node (ref "IC2") (pin "15") (pinfunction "#SUSPEND_15") (pintype "output"))
    )
    (net (code "84") (name "unconnected-(IC2A-CTS-Pad18)") (class "Default")
      (node (ref "IC2") (pin "18") (pinfunction "CTS_18") (pintype "input"))
    )
    (net (code "85") (name "unconnected-(IC2A-DCD-Pad24)") (class "Default")
      (node (ref "IC2") (pin "24") (pinfunction "DCD_24") (pintype "input"))
    )
    (net (code "86") (name "unconnected-(IC2A-DSR-Pad22)") (class "Default")
      (node (ref "IC2") (pin "22") (pinfunction "DSR_22") (pintype "input"))
    )
    (net (code "87") (name "unconnected-(IC2A-GPIO0{slash}TXLED-Pad14)") (class "Default")
      (node (ref "IC2") (pin "14") (pinfunction "GPIO0/TXLED_14") (pintype "bidirectional"))
    )
    (net (code "88") (name "unconnected-(IC2A-GPIO1{slash}RXLED-Pad13)") (class "Default")
      (node (ref "IC2") (pin "13") (pinfunction "GPIO1/RXLED_13") (pintype "bidirectional"))
    )
    (net (code "89") (name "unconnected-(IC2A-GPIO2-Pad12)") (class "Default")
      (node (ref "IC2") (pin "12") (pinfunction "GPIO2_12") (pintype "bidirectional"))
    )
    (net (code "90") (name "unconnected-(IC2A-GPIO3-Pad11)") (class "Default")
      (node (ref "IC2") (pin "11") (pinfunction "GPIO3_11") (pintype "bidirectional"))
    )
    (net (code "91") (name "unconnected-(IC2A-NC-Pad10)") (class "Default")
      (node (ref "IC2") (pin "10") (pinfunction "NC_10") (pintype "no_connect"))
    )
    (net (code "92") (name "unconnected-(IC2A-RI-Pad1)") (class "Default")
      (node (ref "IC2") (pin "1") (pinfunction "RI_1") (pintype "input"))
    )
    (net (code "93") (name "unconnected-(IC2A-SUSPEND-Pad17)") (class "Default")
      (node (ref "IC2") (pin "17") (pinfunction "SUSPEND_17") (pintype "output"))
    )
    (net (code "94") (name "unconnected-(J4-ID-Pad4)") (class "Default")
      (node (ref "J4") (pin "4") (pinfunction "ID_4") (pintype "passive"))
    )
    (net (code "95") (name "unconnected-(PS1-DNC8-Pad8)") (class "Default")
      (node (ref "PS1") (pin "8") (pinfunction "DNC8_8") (pintype "output"))
    )
    (net (code "96") (name "unconnected-(PS1-DNC9-Pad9)") (class "Default")
      (node (ref "PS1") (pin "9") (pinfunction "DNC9_9") (pintype "output"))
    )
    (net (code "97") (name "unconnected-(PS1-DNC10-Pad10)") (class "Default")
      (node (ref "PS1") (pin "10") (pinfunction "DNC10_10") (pintype "output"))
    )
    (net (code "98") (name "unconnected-(PS1-PGOOD-Pad5)") (class "Default")
      (node (ref "PS1") (pin "5") (pinfunction "PGOOD_5") (pintype "output"))
    )
    (net (code "99") (name "unconnected-(U1-STBY-Pad8)") (class "Default")
      (node (ref "U1") (pin "8") (pinfunction "STBY_8") (pintype "input"))
    )
    (net (code "100") (name "unconnected-(U3-PWM-Pad14)") (class "Default")
      (node (ref "U3") (pin "14") (pinfunction "PWM_14") (pintype "output"))
    )
    (net (code "101") (name "unconnected-(U3-TEST1-Pad5)") (class "Default")
      (node (ref "U3") (pin "5") (pinfunction "TEST1_5") (pintype "bidirectional"))
    )
    (net (code "102") (name "unconnected-(U3-TEST2-Pad6)") (class "Default")
      (node (ref "U3") (pin "6") (pinfunction "TEST2_6") (pintype "bidirectional"))
    )
    (net (code "103") (name "unconnected-(U3-TEST3-Pad7)") (class "Default")
      (node (ref "U3") (pin "7") (pinfunction "TEST3_7") (pintype "bidirectional"))
    )
    (net (code "104") (name "unconnected-(U3-TEST4-Pad8)") (class "Default")
      (node (ref "U3") (pin "8") (pinfunction "TEST4_8") (pintype "bidirectional"))
    )
    (net (code "105") (name "unconnected-(U3-TEST5-Pad9)") (class "Default")
      (node (ref "U3") (pin "9") (pinfunction "TEST5_9") (pintype "bidirectional"))
    )
    (net (code "106") (name "unconnected-(U3-TEST6-Pad10)") (class "Default")
      (node (ref "U3") (pin "10") (pinfunction "TEST6_10") (pintype "bidirectional"))
    )
    (net (code "107") (name "unconnected-(X2-CLK-Pad20)") (class "Default")
      (node (ref "X2") (pin "20") (pinfunction "CLK_20") (pintype "bidirectional"))
    )
    (net (code "108") (name "unconnected-(X2-CMD-Pad19)") (class "Default")
      (node (ref "X2") (pin "19") (pinfunction "CMD_19") (pintype "bidirectional"))
    )
    (net (code "109") (name "unconnected-(X2-I34{slash}A1_6-Pad6)") (class "Default")
      (node (ref "X2") (pin "6") (pinfunction "I34/A1_6_6") (pintype "bidirectional"))
    )
    (net (code "110") (name "unconnected-(X2-I35{slash}A1_7-Pad7)") (class "Default")
      (node (ref "X2") (pin "7") (pinfunction "I35/A1_7_7") (pintype "bidirectional"))
    )
    (net (code "111") (name "unconnected-(X2-IO23-Pad37)") (class "Default")
      (node (ref "X2") (pin "37") (pinfunction "IO23_37") (pintype "bidirectional"))
    )
    (net (code "112") (name "unconnected-(X2-SD0-Pad21)") (class "Default")
      (node (ref "X2") (pin "21") (pinfunction "SD0_21") (pintype "bidirectional"))
    )
    (net (code "113") (name "unconnected-(X2-SD1-Pad22)") (class "Default")
      (node (ref "X2") (pin "22") (pinfunction "SD1_22") (pintype "bidirectional"))
    )
    (net (code "114") (name "unconnected-(X2-SD2-Pad17)") (class "Default")
      (node (ref "X2") (pin "17") (pinfunction "SD2_17") (pintype "bidirectional"))
    )
    (net (code "115") (name "unconnected-(X2-SD3-Pad18)") (class "Default")
      (node (ref "X2") (pin "18") (pinfunction "SD3_18") (pintype "bidirectional"))
    )
  )
)
